# STC12_CH340E.net
KiCad netlist of a schematic drawn in Altium Designer
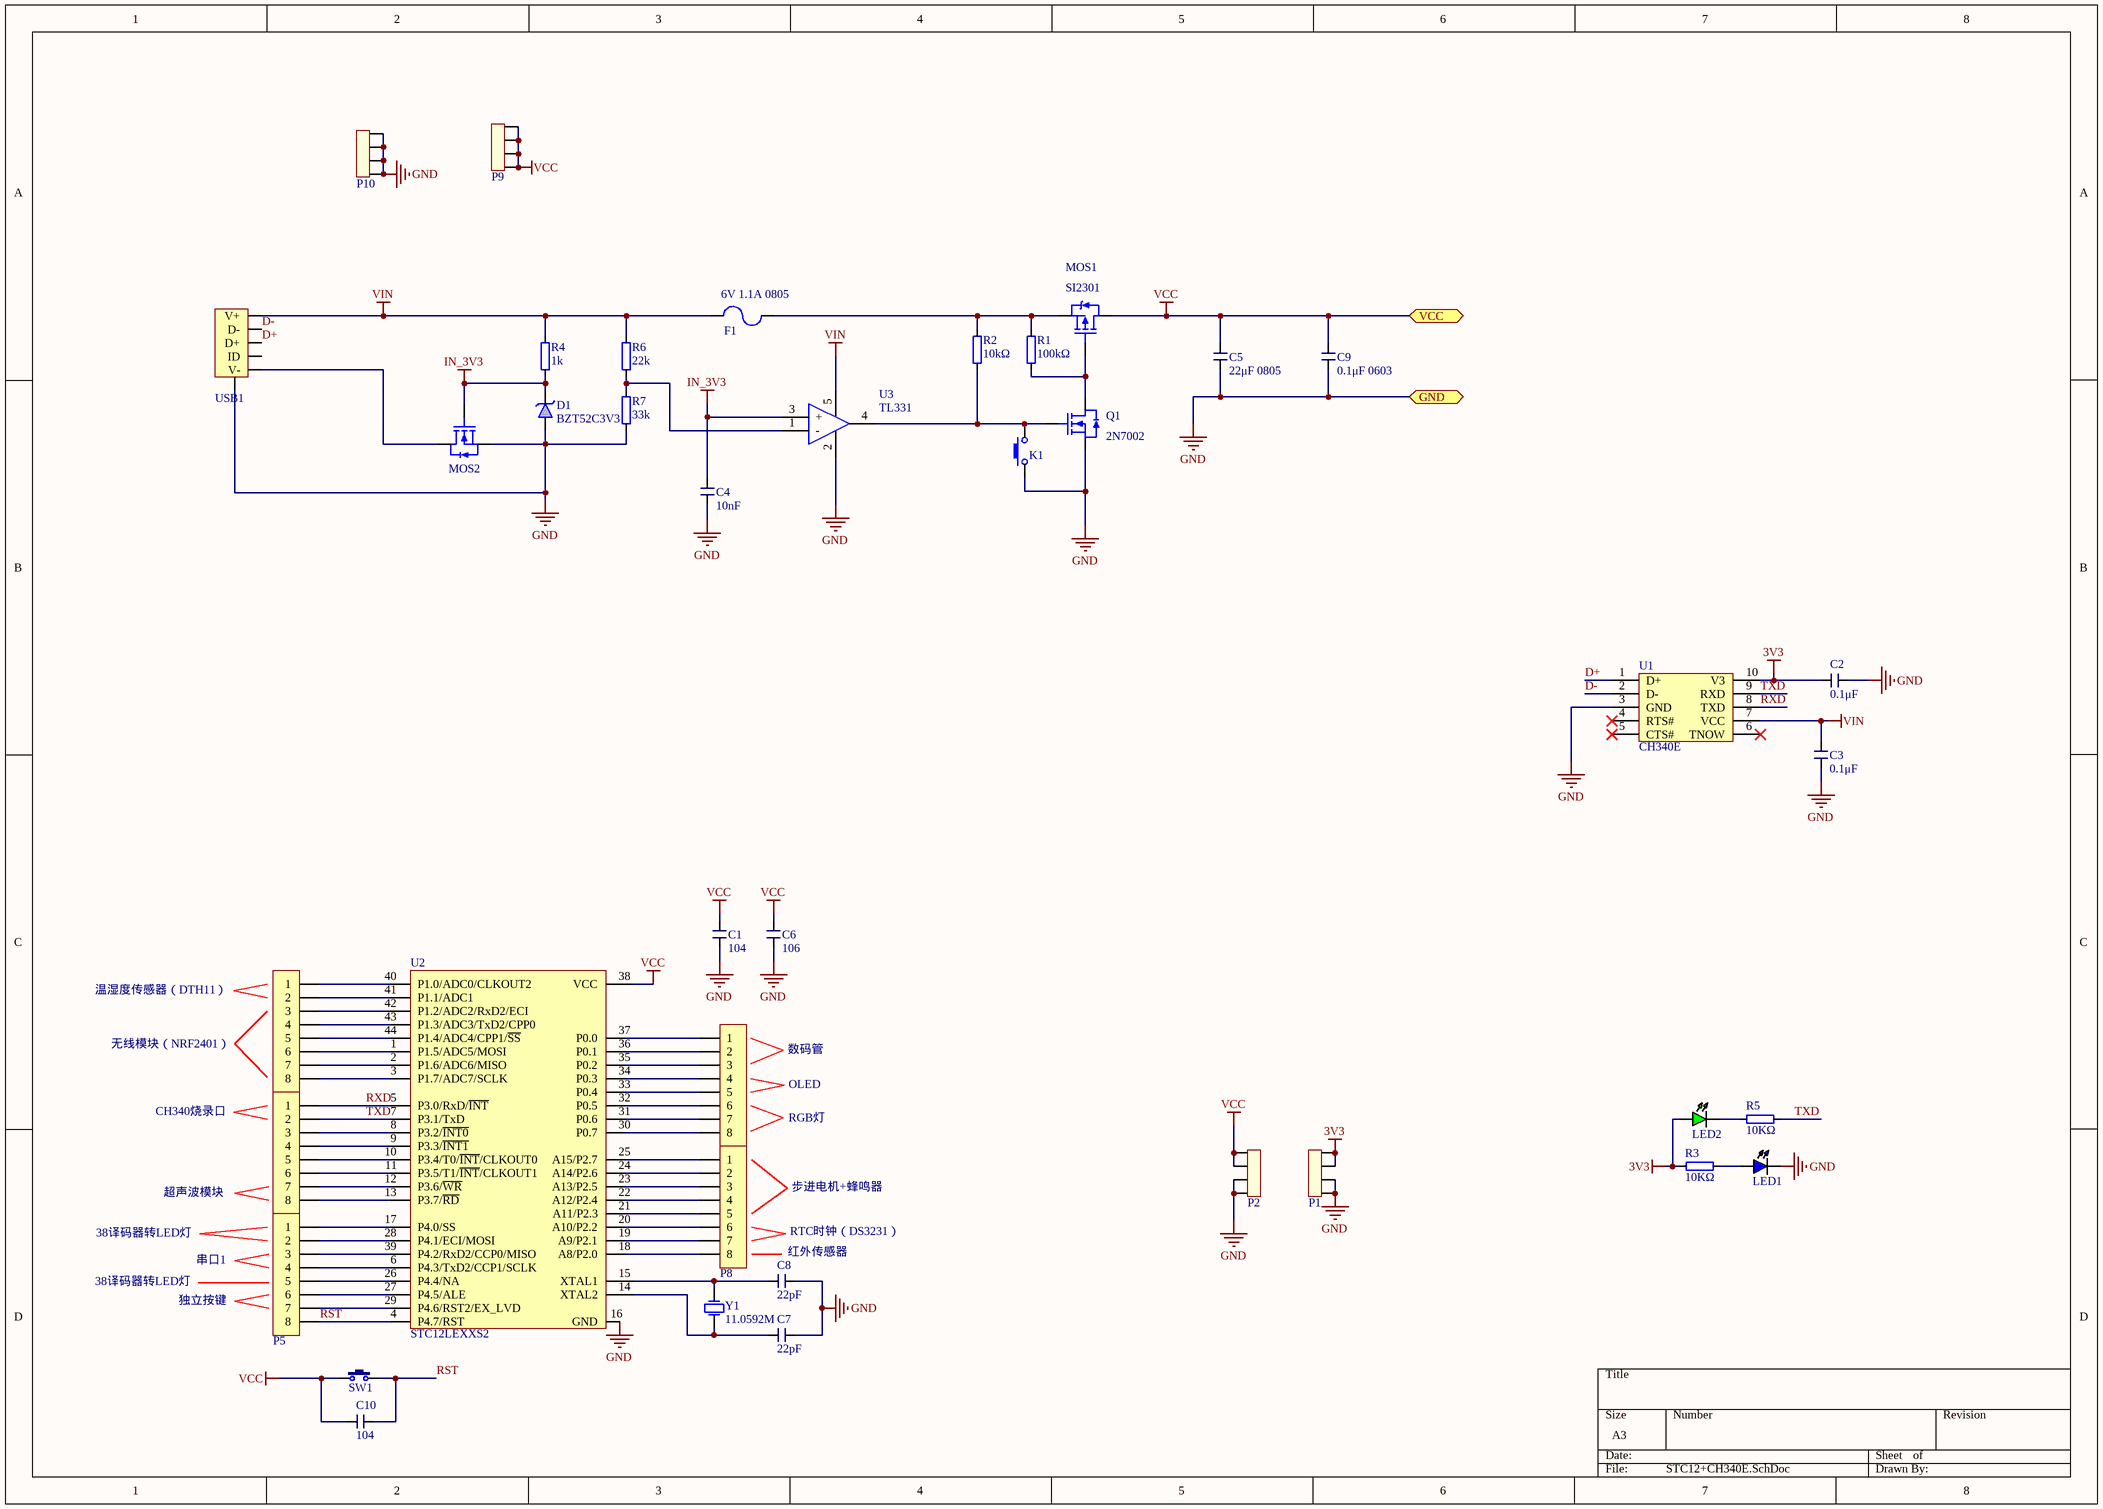
[diagram p0: STC12+CH340E.SchDoc]

(export (version "E")
  (design (tool "Eeschema 10.0.6"))
  (components
    (comp (ref "C1") (value "104") (footprint "C_0603") (libsource (lib "节能库") (part "C_0603")))
    (comp (ref "C2") (value "0.1μF") (footprint "C_0603") (libsource (lib "节能库") (part "C_0603")))
    (comp (ref "C3") (value "0.1μF") (footprint "C_0603") (libsource (lib "节能库") (part "C_0603")))
    (comp (ref "C4") (value "10nF") (footprint "C_0603") (libsource (lib "节能库") (part "C_0603")))
    (comp (ref "C5") (value "22μF 0805") (footprint "C_0805") (libsource (lib "节能库") (part "C_0805")))
    (comp (ref "C6") (value "106") (footprint "C_0603") (libsource (lib "节能库") (part "C_0603")))
    (comp (ref "C7") (value "22pF") (footprint "C_0603") (libsource (lib "节能库") (part "C_0603")))
    (comp (ref "C8") (value "22pF") (footprint "C_0603") (libsource (lib "节能库") (part "C_0603")))
    (comp (ref "C9") (value "0.1μF 0603") (footprint "C_0603") (libsource (lib "节能库") (part "C_0603")))
    (comp (ref "C10") (value "104") (footprint "C_0603") (libsource (lib "节能库") (part "C_0603")))
    (comp (ref "D1") (value "BZT52C3V3") (footprint "SOD_123") (libsource (lib "节能库") (part "BZT52CxVx")))
    (comp (ref "F1") (value "6V 1.1A 0805") (footprint "FB_0805") (libsource (lib "节能库") (part "FUSE_0805")))
    (comp (ref "K1")
      (value "TACT SWITCH_2_SMD")
      (footprint "TACT SWITCH_2_SMD")
      (libsource (lib "节能库") (part "TACT SWITCH_2_SMD"))
    )
    (comp (ref "LED1")
      (value "LED_0603-B")
      (footprint "LED_0603-B")
      (libsource (lib "节能库") (part "LED_0603-B"))
    )
    (comp (ref "LED2")
      (value "LED_0603-G")
      (footprint "LED_0603-G")
      (libsource (lib "节能库") (part "LED_0603-G"))
    )
    (comp (ref "MOS1") (value "SI2301") (footprint "SOT_23_3") (libsource (lib "节能库") (part "SI2301")))
    (comp (ref "MOS2") (value "AO3400A") (footprint "SOT_23_3") (libsource (lib "节能库") (part "AO3400A")))
    (comp (ref "P1") (value "PIN4") (footprint "PIN_4") (libsource (lib "") (part "PIN4_2")))
    (comp (ref "P2") (value "PIN4") (footprint "PIN_4") (libsource (lib "") (part "PIN4_1")))
    (comp (ref "P3")
      (value "HDR-1X8")
      (footprint "HDR-1X8")
      (description "8P接插件")
      (fields (field (name "版权归属") "源创客"))
      (libsource (lib "接插件") (part "Header 8"))
    )
    (comp (ref "P4")
      (value "HDR-1X8")
      (footprint "HDR-1X8")
      (description "8P接插件")
      (fields (field (name "版权归属") "源创客"))
      (libsource (lib "") (part "Header 8_1"))
    )
    (comp (ref "P5")
      (value "HDR-1X8")
      (footprint "HDR-1X8")
      (description "8P接插件")
      (fields (field (name "版权归属") "源创客"))
      (libsource (lib "接插件") (part "Header 8"))
    )
    (comp (ref "P7")
      (value "HDR-1X8")
      (footprint "HDR-1X8")
      (description "8P接插件")
      (fields (field (name "版权归属") "源创客"))
      (libsource (lib "接插件") (part "Header 8"))
    )
    (comp (ref "P8")
      (value "HDR-1X8")
      (footprint "HDR-1X8")
      (description "8P接插件")
      (fields (field (name "版权归属") "源创客"))
      (libsource (lib "") (part "Header 8_1"))
    )
    (comp (ref "P9") (value "PIN4") (footprint "PIN_4") (libsource (lib "节能库") (part "PIN4")))
    (comp (ref "P10") (value "PIN4") (footprint "PIN_4") (libsource (lib "节能库") (part "PIN4")))
    (comp (ref "Q1") (value "2N7002") (footprint "SOT_23_3") (libsource (lib "节能库") (part "2N7002")))
    (comp (ref "R1") (value "100kΩ") (footprint "R_0603") (libsource (lib "节能库") (part "R_0603")))
    (comp (ref "R2") (value "10kΩ") (footprint "R_0603") (libsource (lib "节能库") (part "R_0603")))
    (comp (ref "R3") (value "10KΩ") (footprint "R_0603") (libsource (lib "节能库") (part "R_0603")))
    (comp (ref "R4") (value "1k") (footprint "R_0603") (libsource (lib "节能库") (part "R_0603")))
    (comp (ref "R5") (value "10KΩ") (footprint "R_0603") (libsource (lib "节能库") (part "R_0603")))
    (comp (ref "R6") (value "22k") (footprint "R_0603") (libsource (lib "节能库") (part "R_0603")))
    (comp (ref "R7") (value "33k") (footprint "R_0603") (libsource (lib "节能库") (part "R_0603")))
    (comp (ref "SW1")
      (value "3x6x5")
      (footprint "TSW SMD-3*6*2.5")
      (description "3x6轻触开关")
      (fields (field (name "版权归属") "源创客"))
      (libsource (lib "按键-开关") (part "TSW 3x6"))
    )
    (comp (ref "U1") (value "CH340E") (footprint "MSOP_10") (libsource (lib "节能库") (part "CH340E")))
    (comp (ref "U2")
      (value "STC12LEXXS2")
      (footprint "LQFP_44")
      (libsource (lib "节能库") (part "STC12LE5AXXS2 - LQPF44"))
    )
    (comp (ref "U3") (value "TL331") (footprint "SOT_23_5") (libsource (lib "节能库") (part "TL331")))
    (comp (ref "USB1")
      (value "MICRO USB B")
      (footprint "MICRO USB B")
      (libsource (lib "节能库") (part "MICRO USB B"))
    )
    (comp (ref "Y1")
      (value "11.0592M")
      (footprint "Crystal_HC_49US")
      (libsource (lib "节能库") (part "Crystal_HC_49US"))
    )
  )
  (nets
    (net (code "1") (name "/D+") (class "Default")
      (node (ref "U1") (pin "1") (pinfunction "D+_1") (pintype "passive"))
      (node (ref "USB1") (pin "3") (pinfunction "D+_3") (pintype "passive"))
    )
    (net (code "2") (name "/D-") (class "Default")
      (node (ref "U1") (pin "2") (pinfunction "D-_2") (pintype "passive"))
      (node (ref "USB1") (pin "2") (pinfunction "D-_2") (pintype "passive"))
    )
    (net (code "3") (name "/RST") (class "Default")
      (node (ref "C10") (pin "2") (pinfunction "2_2") (pintype "passive"))
      (node (ref "P5") (pin "8") (pinfunction "8_8") (pintype "passive"))
      (node (ref "SW1") (pin "2") (pinfunction "2_2") (pintype "passive"))
      (node (ref "U2") (pin "4") (pinfunction "P4.7/RST_4") (pintype "passive"))
    )
    (net (code "4") (name "/RXD") (class "Default")
      (node (ref "P7") (pin "1") (pinfunction "1_1") (pintype "passive"))
      (node (ref "U1") (pin "8") (pinfunction "TXD_8") (pintype "passive"))
      (node (ref "U2") (pin "5") (pinfunction "P3.0/RxD/~{INT}_5") (pintype "passive"))
    )
    (net (code "5") (name "/TXD") (class "Default")
      (node (ref "P7") (pin "2") (pinfunction "2_2") (pintype "passive"))
      (node (ref "R5") (pin "2") (pintype "passive"))
      (node (ref "U1") (pin "9") (pinfunction "RXD_9") (pintype "passive"))
      (node (ref "U2") (pin "7") (pinfunction "P3.1/TxD_7") (pintype "passive"))
    )
    (net (code "6") (name "3V3") (class "Default")
      (node (ref "C2") (pin "2") (pinfunction "2_2") (pintype "passive"))
      (node (ref "LED2") (pin "1") (pinfunction "1_1") (pintype "passive"))
      (node (ref "P1") (pin "3") (pinfunction "3_3") (pintype "passive"))
      (node (ref "P1") (pin "4") (pinfunction "4_4") (pintype "passive"))
      (node (ref "R3") (pin "1") (pintype "passive"))
      (node (ref "U1") (pin "10") (pinfunction "V3_10") (pintype "passive"))
    )
    (net (code "7") (name "GND") (class "Default")
      (node (ref "C1") (pin "2") (pinfunction "2_2") (pintype "passive"))
      (node (ref "C2") (pin "1") (pinfunction "1_1") (pintype "passive"))
      (node (ref "C3") (pin "1") (pinfunction "1_1") (pintype "passive"))
      (node (ref "C4") (pin "2") (pinfunction "2_2") (pintype "passive"))
      (node (ref "C5") (pin "2") (pinfunction "2_2") (pintype "passive"))
      (node (ref "C6") (pin "2") (pinfunction "2_2") (pintype "passive"))
      (node (ref "C7") (pin "2") (pinfunction "2_2") (pintype "passive"))
      (node (ref "C8") (pin "2") (pinfunction "2_2") (pintype "passive"))
      (node (ref "C9") (pin "2") (pinfunction "2_2") (pintype "passive"))
      (node (ref "D1") (pin "1") (pinfunction "A_1") (pintype "passive"))
      (node (ref "K1") (pin "1") (pinfunction "1_1") (pintype "passive"))
      (node (ref "LED1") (pin "2") (pinfunction "2_2") (pintype "passive"))
      (node (ref "MOS2") (pin "2") (pinfunction "S_2") (pintype "passive"))
      (node (ref "P1") (pin "1") (pinfunction "1_1") (pintype "passive"))
      (node (ref "P1") (pin "2") (pinfunction "2_2") (pintype "passive"))
      (node (ref "P10") (pin "1") (pinfunction "1_1") (pintype "passive"))
      (node (ref "P10") (pin "2") (pinfunction "2_2") (pintype "passive"))
      (node (ref "P10") (pin "3") (pinfunction "3_3") (pintype "passive"))
      (node (ref "P10") (pin "4") (pinfunction "4_4") (pintype "passive"))
      (node (ref "P2") (pin "1") (pinfunction "1_1") (pintype "passive"))
      (node (ref "P2") (pin "2") (pinfunction "2_2") (pintype "passive"))
      (node (ref "Q1") (pin "2") (pinfunction "S_2") (pintype "passive"))
      (node (ref "R7") (pin "1") (pintype "passive"))
      (node (ref "U1") (pin "3") (pinfunction "GND_3") (pintype "passive"))
      (node (ref "U2") (pin "16") (pinfunction "GND_16") (pintype "passive"))
      (node (ref "U3") (pin "2") (pinfunction "GND_2") (pintype "passive"))
      (node (ref "USB1") (pin "0") (pinfunction "GND_0") (pintype "passive"))
    )
    (net (code "8") (name "IN_3V3") (class "Default")
      (node (ref "C4") (pin "1") (pinfunction "1_1") (pintype "passive"))
      (node (ref "D1") (pin "2") (pinfunction "K_2") (pintype "passive"))
      (node (ref "MOS2") (pin "1") (pinfunction "G_1") (pintype "passive"))
      (node (ref "R4") (pin "1") (pintype "passive"))
      (node (ref "U3") (pin "3") (pinfunction "+_3") (pintype "passive"))
    )
    (net (code "9") (name "Net-(LED1-Pad1)") (class "Default")
      (node (ref "LED1") (pin "1") (pinfunction "1_1") (pintype "passive"))
      (node (ref "R3") (pin "2") (pintype "passive"))
    )
    (net (code "10") (name "Net-(LED2-Pad2)") (class "Default")
      (node (ref "LED2") (pin "2") (pinfunction "2_2") (pintype "passive"))
      (node (ref "R5") (pin "1") (pintype "passive"))
    )
    (net (code "11") (name "Net-(MOS1-G)") (class "Default")
      (node (ref "MOS1") (pin "1") (pinfunction "G_1") (pintype "passive"))
      (node (ref "Q1") (pin "3") (pinfunction "D_3") (pintype "passive"))
      (node (ref "R1") (pin "1") (pintype "passive"))
    )
    (net (code "12") (name "Net-(MOS1-S)") (class "Default")
      (node (ref "F1") (pin "2") (pinfunction "2_2") (pintype "passive"))
      (node (ref "MOS1") (pin "2") (pinfunction "S_2") (pintype "passive"))
      (node (ref "R1") (pin "2") (pintype "passive"))
      (node (ref "R2") (pin "2") (pintype "passive"))
    )
    (net (code "13") (name "Net-(MOS2-D)") (class "Default")
      (node (ref "MOS2") (pin "3") (pinfunction "D_3") (pintype "passive"))
      (node (ref "USB1") (pin "5") (pinfunction "V-_5") (pintype "passive"))
    )
    (net (code "14") (name "Net-(Q1-G)") (class "Default")
      (node (ref "K1") (pin "2") (pinfunction "2_2") (pintype "passive"))
      (node (ref "Q1") (pin "1") (pinfunction "G_1") (pintype "passive"))
      (node (ref "R2") (pin "1") (pintype "passive"))
      (node (ref "U3") (pin "4") (pinfunction "OUT_4") (pintype "passive"))
    )
    (net (code "15") (name "Net-(U2-A8{slash}P2.0)") (class "Default")
      (node (ref "P8") (pin "8") (pinfunction "8_8") (pintype "passive"))
      (node (ref "U2") (pin "18") (pinfunction "A8/P2.0_18") (pintype "passive"))
    )
    (net (code "16") (name "Net-(U2-A9{slash}P2.1)") (class "Default")
      (node (ref "P8") (pin "7") (pinfunction "7_7") (pintype "passive"))
      (node (ref "U2") (pin "19") (pinfunction "A9/P2.1_19") (pintype "passive"))
    )
    (net (code "17") (name "Net-(U2-A10{slash}P2.2)") (class "Default")
      (node (ref "P8") (pin "6") (pinfunction "6_6") (pintype "passive"))
      (node (ref "U2") (pin "20") (pinfunction "A10/P2.2_20") (pintype "passive"))
    )
    (net (code "18") (name "Net-(U2-A11{slash}P2.3)") (class "Default")
      (node (ref "P8") (pin "5") (pinfunction "5_5") (pintype "passive"))
      (node (ref "U2") (pin "21") (pinfunction "A11/P2.3_21") (pintype "passive"))
    )
    (net (code "19") (name "Net-(U2-A12{slash}P2.4)") (class "Default")
      (node (ref "P8") (pin "4") (pinfunction "4_4") (pintype "passive"))
      (node (ref "U2") (pin "22") (pinfunction "A12/P2.4_22") (pintype "passive"))
    )
    (net (code "20") (name "Net-(U2-A13{slash}P2.5)") (class "Default")
      (node (ref "P8") (pin "3") (pinfunction "3_3") (pintype "passive"))
      (node (ref "U2") (pin "23") (pinfunction "A13/P2.5_23") (pintype "passive"))
    )
    (net (code "21") (name "Net-(U2-A14{slash}P2.6)") (class "Default")
      (node (ref "P8") (pin "2") (pinfunction "2_2") (pintype "passive"))
      (node (ref "U2") (pin "24") (pinfunction "A14/P2.6_24") (pintype "passive"))
    )
    (net (code "22") (name "Net-(U2-A15{slash}P2.7)") (class "Default")
      (node (ref "P8") (pin "1") (pinfunction "1_1") (pintype "passive"))
      (node (ref "U2") (pin "25") (pinfunction "A15/P2.7_25") (pintype "passive"))
    )
    (net (code "23") (name "Net-(U2-P0.0)") (class "Default")
      (node (ref "P4") (pin "1") (pinfunction "1_1") (pintype "passive"))
      (node (ref "U2") (pin "37") (pinfunction "P0.0_37") (pintype "passive"))
    )
    (net (code "24") (name "Net-(U2-P0.1)") (class "Default")
      (node (ref "P4") (pin "2") (pinfunction "2_2") (pintype "passive"))
      (node (ref "U2") (pin "36") (pinfunction "P0.1_36") (pintype "passive"))
    )
    (net (code "25") (name "Net-(U2-P0.2)") (class "Default")
      (node (ref "P4") (pin "3") (pinfunction "3_3") (pintype "passive"))
      (node (ref "U2") (pin "35") (pinfunction "P0.2_35") (pintype "passive"))
    )
    (net (code "26") (name "Net-(U2-P0.3)") (class "Default")
      (node (ref "P4") (pin "4") (pinfunction "4_4") (pintype "passive"))
      (node (ref "U2") (pin "34") (pinfunction "P0.3_34") (pintype "passive"))
    )
    (net (code "27") (name "Net-(U2-P0.4)") (class "Default")
      (node (ref "P4") (pin "5") (pinfunction "5_5") (pintype "passive"))
      (node (ref "U2") (pin "33") (pinfunction "P0.4_33") (pintype "passive"))
    )
    (net (code "28") (name "Net-(U2-P0.5)") (class "Default")
      (node (ref "P4") (pin "6") (pinfunction "6_6") (pintype "passive"))
      (node (ref "U2") (pin "32") (pinfunction "P0.5_32") (pintype "passive"))
    )
    (net (code "29") (name "Net-(U2-P0.6)") (class "Default")
      (node (ref "P4") (pin "7") (pinfunction "7_7") (pintype "passive"))
      (node (ref "U2") (pin "31") (pinfunction "P0.6_31") (pintype "passive"))
    )
    (net (code "30") (name "Net-(U2-P0.7)") (class "Default")
      (node (ref "P4") (pin "8") (pinfunction "8_8") (pintype "passive"))
      (node (ref "U2") (pin "30") (pinfunction "P0.7_30") (pintype "passive"))
    )
    (net (code "31") (name "Net-(U2-P1.0{slash}ADC0{slash}CLKOUT2)") (class "Default")
      (node (ref "P3") (pin "1") (pinfunction "1_1") (pintype "passive"))
      (node (ref "U2") (pin "40") (pinfunction "P1.0/ADC0/CLKOUT2_40") (pintype "passive"))
    )
    (net (code "32") (name "Net-(U2-P1.1{slash}ADC1)") (class "Default")
      (node (ref "P3") (pin "2") (pinfunction "2_2") (pintype "passive"))
      (node (ref "U2") (pin "41") (pinfunction "P1.1/ADC1_41") (pintype "passive"))
    )
    (net (code "33") (name "Net-(U2-P1.2{slash}ADC2{slash}RxD2{slash}ECI)") (class "Default")
      (node (ref "P3") (pin "3") (pinfunction "3_3") (pintype "passive"))
      (node (ref "U2") (pin "42") (pinfunction "P1.2/ADC2/RxD2/ECI_42") (pintype "passive"))
    )
    (net (code "34") (name "Net-(U2-P1.3{slash}ADC3{slash}TxD2{slash}CPP0)") (class "Default")
      (node (ref "P3") (pin "4") (pinfunction "4_4") (pintype "passive"))
      (node (ref "U2") (pin "43") (pinfunction "P1.3/ADC3/TxD2/CPP0_43") (pintype "passive"))
    )
    (net (code "35") (name "Net-(U2-P1.4{slash}ADC4{slash}CPP1{slash}~{SS})") (class "Default")
      (node (ref "P3") (pin "5") (pinfunction "5_5") (pintype "passive"))
      (node (ref "U2") (pin "44") (pinfunction "P1.4/ADC4/CPP1/~{SS}_44") (pintype "passive"))
    )
    (net (code "36") (name "Net-(U2-P1.5{slash}ADC5{slash}MOSI)") (class "Default")
      (node (ref "P3") (pin "6") (pinfunction "6_6") (pintype "passive"))
      (node (ref "U2") (pin "1") (pinfunction "P1.5/ADC5/MOSI_1") (pintype "passive"))
    )
    (net (code "37") (name "Net-(U2-P1.6{slash}ADC6{slash}MISO)") (class "Default")
      (node (ref "P3") (pin "7") (pinfunction "7_7") (pintype "passive"))
      (node (ref "U2") (pin "2") (pinfunction "P1.6/ADC6/MISO_2") (pintype "passive"))
    )
    (net (code "38") (name "Net-(U2-P1.7{slash}ADC7{slash}SCLK)") (class "Default")
      (node (ref "P3") (pin "8") (pinfunction "8_8") (pintype "passive"))
      (node (ref "U2") (pin "3") (pinfunction "P1.7/ADC7/SCLK_3") (pintype "passive"))
    )
    (net (code "39") (name "Net-(U2-P3.2{slash}~{INT0})") (class "Default")
      (node (ref "P7") (pin "3") (pinfunction "3_3") (pintype "passive"))
      (node (ref "U2") (pin "8") (pinfunction "P3.2/~{INT0}_8") (pintype "passive"))
    )
    (net (code "40") (name "Net-(U2-P3.3{slash}~{INT1})") (class "Default")
      (node (ref "P7") (pin "4") (pinfunction "4_4") (pintype "passive"))
      (node (ref "U2") (pin "9") (pinfunction "P3.3/~{INT1}_9") (pintype "passive"))
    )
    (net (code "41") (name "Net-(U2-P3.4{slash}T0{slash}~{INT}{slash}CLKOUT0)") (class "Default")
      (node (ref "P7") (pin "5") (pinfunction "5_5") (pintype "passive"))
      (node (ref "U2") (pin "10") (pinfunction "P3.4/T0/~{INT}/CLKOUT0_10") (pintype "passive"))
    )
    (net (code "42") (name "Net-(U2-P3.5{slash}T1{slash}~{INT}{slash}CLKOUT1)") (class "Default")
      (node (ref "P7") (pin "6") (pinfunction "6_6") (pintype "passive"))
      (node (ref "U2") (pin "11") (pinfunction "P3.5/T1/~{INT}/CLKOUT1_11") (pintype "passive"))
    )
    (net (code "43") (name "Net-(U2-P3.6{slash}~{WR})") (class "Default")
      (node (ref "P7") (pin "7") (pinfunction "7_7") (pintype "passive"))
      (node (ref "U2") (pin "12") (pinfunction "P3.6/~{WR}_12") (pintype "passive"))
    )
    (net (code "44") (name "Net-(U2-P3.7{slash}~{RD})") (class "Default")
      (node (ref "P7") (pin "8") (pinfunction "8_8") (pintype "passive"))
      (node (ref "U2") (pin "13") (pinfunction "P3.7/~{RD}_13") (pintype "passive"))
    )
    (net (code "45") (name "Net-(U2-P4.0{slash}SS)") (class "Default")
      (node (ref "P5") (pin "1") (pinfunction "1_1") (pintype "passive"))
      (node (ref "U2") (pin "17") (pinfunction "P4.0/SS_17") (pintype "passive"))
    )
    (net (code "46") (name "Net-(U2-P4.1{slash}ECI{slash}MOSI)") (class "Default")
      (node (ref "P5") (pin "2") (pinfunction "2_2") (pintype "passive"))
      (node (ref "U2") (pin "28") (pinfunction "P4.1/ECI/MOSI_28") (pintype "passive"))
    )
    (net (code "47") (name "Net-(U2-P4.2{slash}RxD2{slash}CCP0{slash}MISO)") (class "Default")
      (node (ref "P5") (pin "3") (pinfunction "3_3") (pintype "passive"))
      (node (ref "U2") (pin "39") (pinfunction "P4.2/RxD2/CCP0/MISO_39") (pintype "passive"))
    )
    (net (code "48") (name "Net-(U2-P4.3{slash}TxD2{slash}CCP1{slash}SCLK)") (class "Default")
      (node (ref "P5") (pin "4") (pinfunction "4_4") (pintype "passive"))
      (node (ref "U2") (pin "6") (pinfunction "P4.3/TxD2/CCP1/SCLK_6") (pintype "passive"))
    )
    (net (code "49") (name "Net-(U2-P4.4{slash}NA)") (class "Default")
      (node (ref "P5") (pin "5") (pinfunction "5_5") (pintype "passive"))
      (node (ref "U2") (pin "26") (pinfunction "P4.4/NA_26") (pintype "passive"))
    )
    (net (code "50") (name "Net-(U2-P4.5{slash}ALE)") (class "Default")
      (node (ref "P5") (pin "6") (pinfunction "6_6") (pintype "passive"))
      (node (ref "U2") (pin "27") (pinfunction "P4.5/ALE_27") (pintype "passive"))
    )
    (net (code "51") (name "Net-(U2-P4.6{slash}RST2{slash}EX_LVD)") (class "Default")
      (node (ref "P5") (pin "7") (pinfunction "7_7") (pintype "passive"))
      (node (ref "U2") (pin "29") (pinfunction "P4.6/RST2/EX_LVD_29") (pintype "passive"))
    )
    (net (code "52") (name "Net-(U2-XTAL1)") (class "Default")
      (node (ref "C8") (pin "1") (pinfunction "1_1") (pintype "passive"))
      (node (ref "U2") (pin "15") (pinfunction "XTAL1_15") (pintype "passive"))
      (node (ref "Y1") (pin "2") (pinfunction "OSC2_2") (pintype "passive"))
    )
    (net (code "53") (name "Net-(U2-XTAL2)") (class "Default")
      (node (ref "C7") (pin "1") (pinfunction "1_1") (pintype "passive"))
      (node (ref "U2") (pin "14") (pinfunction "XTAL2_14") (pintype "passive"))
      (node (ref "Y1") (pin "1") (pinfunction "OSC1_1") (pintype "passive"))
    )
    (net (code "54") (name "Net-(U3--)") (class "Default")
      (node (ref "R6") (pin "1") (pintype "passive"))
      (node (ref "R7") (pin "2") (pintype "passive"))
      (node (ref "U3") (pin "1") (pinfunction "-_1") (pintype "passive"))
    )
    (net (code "55") (name "VCC") (class "Default")
      (node (ref "C1") (pin "1") (pinfunction "1_1") (pintype "passive"))
      (node (ref "C10") (pin "1") (pinfunction "1_1") (pintype "passive"))
      (node (ref "C5") (pin "1") (pinfunction "1_1") (pintype "passive"))
      (node (ref "C6") (pin "1") (pinfunction "1_1") (pintype "passive"))
      (node (ref "C9") (pin "1") (pinfunction "1_1") (pintype "passive"))
      (node (ref "MOS1") (pin "3") (pinfunction "D_3") (pintype "passive"))
      (node (ref "P2") (pin "3") (pinfunction "3_3") (pintype "passive"))
      (node (ref "P2") (pin "4") (pinfunction "4_4") (pintype "passive"))
      (node (ref "P9") (pin "1") (pinfunction "1_1") (pintype "passive"))
      (node (ref "P9") (pin "2") (pinfunction "2_2") (pintype "passive"))
      (node (ref "P9") (pin "3") (pinfunction "3_3") (pintype "passive"))
      (node (ref "P9") (pin "4") (pinfunction "4_4") (pintype "passive"))
      (node (ref "SW1") (pin "1") (pinfunction "1_1") (pintype "passive"))
      (node (ref "U2") (pin "38") (pinfunction "VCC_38") (pintype "passive"))
    )
    (net (code "56") (name "VIN") (class "Default")
      (node (ref "C3") (pin "2") (pinfunction "2_2") (pintype "passive"))
      (node (ref "F1") (pin "1") (pinfunction "1_1") (pintype "passive"))
      (node (ref "R4") (pin "2") (pintype "passive"))
      (node (ref "R6") (pin "2") (pintype "passive"))
      (node (ref "U1") (pin "7") (pinfunction "VCC_7") (pintype "passive"))
      (node (ref "U3") (pin "5") (pinfunction "VCC_5") (pintype "passive"))
      (node (ref "USB1") (pin "1") (pinfunction "V+_1") (pintype "passive"))
    )
    (net (code "57") (name "unconnected-(U1-CTS#-Pad5)") (class "Default")
      (node (ref "U1") (pin "5") (pinfunction "CTS#_5") (pintype "passive+no_connect"))
    )
    (net (code "58") (name "unconnected-(U1-RTS#-Pad4)") (class "Default")
      (node (ref "U1") (pin "4") (pinfunction "RTS#_4") (pintype "passive+no_connect"))
    )
    (net (code "59") (name "unconnected-(U1-TNOW-Pad6)") (class "Default")
      (node (ref "U1") (pin "6") (pinfunction "TNOW_6") (pintype "passive+no_connect"))
    )
    (net (code "60") (name "unconnected-(USB1-ID-Pad4)") (class "Default")
      (node (ref "USB1") (pin "4") (pinfunction "ID_4") (pintype "passive"))
    )
  )
)
